# ModLCDDisplay.net
KiCad netlist of a schematic drawn in Altium Designer
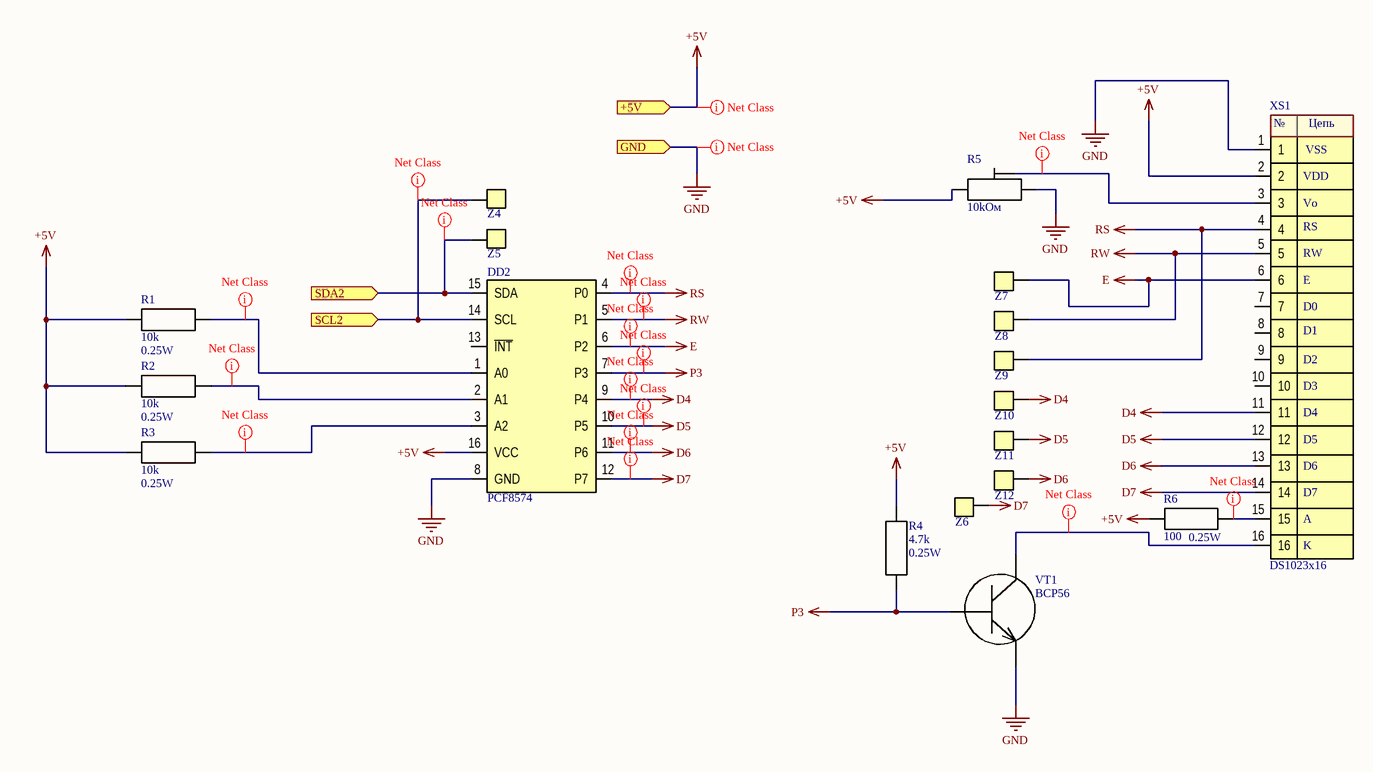
[diagram p0: ModLCDDisplay.SchDoc]

(export (version "E")
  (design (tool "Eeschema 10.0.6"))
  (components
    (comp (ref "DD2")
      (value "PCF8574")
      (footprint "SO-16")
      (fields (field (name "PART NUMBER") "PCF8574DW") (field (name "MANUFACTURER") "Texas Instruments"))
      (libsource (lib "SchlibUGO") (part "PCF8574"))
    )
    (comp (ref "R1")
      (value "10k")
      (footprint "1206")
      (fields
        (field (name "MANUFACTURER") "YAGEO")
        (field (name "PART NUMBER") "RC1206FR-0710KL")
        (field (name "POWER") "0.25W")
      )
      (libsource (lib "SchlibUGO") (part "Resistor"))
    )
    (comp (ref "R2")
      (value "10k")
      (footprint "1206")
      (fields
        (field (name "MANUFACTURER") "YAGEO")
        (field (name "PART NUMBER") "RC1206FR-0710KL")
        (field (name "POWER") "0.25W")
      )
      (libsource (lib "SchlibUGO") (part "Resistor"))
    )
    (comp (ref "R3")
      (value "10k")
      (footprint "1206")
      (fields
        (field (name "MANUFACTURER") "YAGEO")
        (field (name "PART NUMBER") "RC1206FR-0710KL")
        (field (name "POWER") "0.25W")
      )
      (libsource (lib "SchlibUGO") (part "Resistor"))
    )
    (comp (ref "R4")
      (value "4.7k")
      (footprint "1206")
      (fields
        (field (name "MANUFACTURER") "YAGEO")
        (field (name "PART NUMBER") "RC1206JR-074K7L")
        (field (name "POWER") "0.25W")
        (field (name "Comment") "4k7")
      )
      (libsource (lib "SchlibUGO") (part "Resistor"))
    )
    (comp (ref "R5")
      (value "10kОм")
      (footprint "3006P")
      (fields
        (field (name "PART NUMBER") "3006-103-Z-LF")
        (field (name "MANUFACTURER") "Bours")
        (field (name "POWER") "0,125W")
      )
      (libsource (lib "SchlibUGO") (part "POT"))
    )
    (comp (ref "R6")
      (value "100")
      (footprint "1206")
      (fields
        (field (name "MANUFACTURER") "YAGEO")
        (field (name "PART NUMBER") "RC1206FR-07100RL")
        (field (name "POWER") "0.25W")
      )
      (libsource (lib "SchlibUGO") (part "Resistor"))
    )
    (comp (ref "VT1")
      (value "BCP56")
      (footprint "SOT223")
      (fields (field (name "PART NUMBER") "BCP56-16") (field (name "MANUFACTURER") "NXP Semiconductors"))
      (libsource (lib "SchlibUGO") (part "BCP56-16"))
    )
    (comp (ref "XS1")
      (value "DS1023x16")
      (footprint "DS1023-2.54x16x1")
      (fields
        (field (name "MANUFACTURER") "Ningbo connfly electronic")
        (field (name "PART NUMBER") "DS1023-1*16S21")
      )
      (libsource (lib "SchlibUGO") (part "DS1023x2.54x16x1"))
    )
    (comp (ref "Z4") (value "test Point") (footprint "test Point") (libsource (lib "") (part "test Point_1")))
    (comp (ref "Z5") (value "test Point") (footprint "test Point") (libsource (lib "") (part "test Point_1")))
    (comp (ref "Z6")
      (value "test Point")
      (footprint "test Point")
      (libsource (lib "SchlibUGO") (part "test Point"))
    )
    (comp (ref "Z7")
      (value "test Point")
      (footprint "test Point")
      (libsource (lib "SchlibUGO") (part "test Point"))
    )
    (comp (ref "Z8")
      (value "test Point")
      (footprint "test Point")
      (libsource (lib "SchlibUGO") (part "test Point"))
    )
    (comp (ref "Z9")
      (value "test Point")
      (footprint "test Point")
      (libsource (lib "SchlibUGO") (part "test Point"))
    )
    (comp (ref "Z10")
      (value "test Point")
      (footprint "test Point")
      (libsource (lib "SchlibUGO") (part "test Point"))
    )
    (comp (ref "Z11")
      (value "test Point")
      (footprint "test Point")
      (libsource (lib "SchlibUGO") (part "test Point"))
    )
    (comp (ref "Z12")
      (value "test Point")
      (footprint "test Point")
      (libsource (lib "SchlibUGO") (part "test Point"))
    )
  )
  (nets
    (net (code "1") (name "+5V") (class "Default")
      (node (ref "DD2") (pin "16") (pinfunction "VCC_16") (pintype "passive"))
      (node (ref "R1") (pin "1") (pinfunction "1_1") (pintype "passive"))
      (node (ref "R2") (pin "1") (pinfunction "1_1") (pintype "passive"))
      (node (ref "R3") (pin "1") (pinfunction "1_1") (pintype "passive"))
      (node (ref "R4") (pin "2") (pinfunction "2_2") (pintype "passive"))
      (node (ref "R5") (pin "1") (pinfunction "1_1") (pintype "passive"))
      (node (ref "R6") (pin "1") (pinfunction "1_1") (pintype "passive"))
      (node (ref "XS1") (pin "2") (pinfunction "2_2") (pintype "passive"))
    )
    (net (code "2") (name "/SCL2") (class "Default")
      (node (ref "DD2") (pin "14") (pinfunction "SCL_14") (pintype "passive"))
      (node (ref "Z4") (pin "1") (pinfunction "1_1") (pintype "passive"))
    )
    (net (code "3") (name "/SDA2") (class "Default")
      (node (ref "DD2") (pin "15") (pinfunction "SDA_15") (pintype "passive"))
      (node (ref "Z5") (pin "1") (pinfunction "1_1") (pintype "passive"))
    )
    (net (code "4") (name "D4") (class "Default")
      (node (ref "DD2") (pin "9") (pinfunction "P4_9") (pintype "passive"))
      (node (ref "XS1") (pin "11") (pinfunction "11_11") (pintype "passive"))
      (node (ref "Z10") (pin "1") (pinfunction "1_1") (pintype "passive"))
    )
    (net (code "5") (name "D5") (class "Default")
      (node (ref "DD2") (pin "10") (pinfunction "P5_10") (pintype "passive"))
      (node (ref "XS1") (pin "12") (pinfunction "12_12") (pintype "passive"))
      (node (ref "Z11") (pin "1") (pinfunction "1_1") (pintype "passive"))
    )
    (net (code "6") (name "D6") (class "Default")
      (node (ref "DD2") (pin "11") (pinfunction "P6_11") (pintype "passive"))
      (node (ref "XS1") (pin "13") (pinfunction "13_13") (pintype "passive"))
      (node (ref "Z12") (pin "1") (pinfunction "1_1") (pintype "passive"))
    )
    (net (code "7") (name "D7") (class "Default")
      (node (ref "DD2") (pin "12") (pinfunction "P7_12") (pintype "passive"))
      (node (ref "XS1") (pin "14") (pinfunction "14_14") (pintype "passive"))
      (node (ref "Z6") (pin "1") (pinfunction "1_1") (pintype "passive"))
    )
    (net (code "8") (name "E") (class "Default")
      (node (ref "DD2") (pin "6") (pinfunction "P2_6") (pintype "passive"))
      (node (ref "XS1") (pin "6") (pinfunction "6_6") (pintype "passive"))
      (node (ref "Z7") (pin "1") (pinfunction "1_1") (pintype "passive"))
    )
    (net (code "9") (name "GND") (class "Default")
      (node (ref "DD2") (pin "8") (pinfunction "GND_8") (pintype "passive"))
      (node (ref "R5") (pin "3") (pinfunction "3_3") (pintype "passive"))
      (node (ref "VT1") (pin "3") (pinfunction "3_3") (pintype "passive"))
      (node (ref "XS1") (pin "1") (pinfunction "1_1") (pintype "passive"))
    )
    (net (code "10") (name "Net-(DD2-A0)") (class "Default")
      (node (ref "DD2") (pin "1") (pinfunction "A0_1") (pintype "passive"))
      (node (ref "R1") (pin "2") (pinfunction "2_2") (pintype "passive"))
    )
    (net (code "11") (name "Net-(DD2-A1)") (class "Default")
      (node (ref "DD2") (pin "2") (pinfunction "A1_2") (pintype "passive"))
      (node (ref "R2") (pin "2") (pinfunction "2_2") (pintype "passive"))
    )
    (net (code "12") (name "Net-(DD2-A2)") (class "Default")
      (node (ref "DD2") (pin "3") (pinfunction "A2_3") (pintype "passive"))
      (node (ref "R3") (pin "2") (pinfunction "2_2") (pintype "passive"))
    )
    (net (code "13") (name "Net-(R5-Pad2)") (class "Default")
      (node (ref "R5") (pin "2") (pinfunction "2_2") (pintype "passive"))
      (node (ref "XS1") (pin "3") (pinfunction "3_3") (pintype "passive"))
    )
    (net (code "14") (name "Net-(R6-Pad2)") (class "Default")
      (node (ref "R6") (pin "2") (pinfunction "2_2") (pintype "passive"))
      (node (ref "XS1") (pin "15") (pinfunction "15_15") (pintype "passive"))
    )
    (net (code "15") (name "Net-(VT1-Pad2)") (class "Default")
      (node (ref "VT1") (pin "2") (pinfunction "2_2") (pintype "passive"))
      (node (ref "XS1") (pin "16") (pinfunction "16_16") (pintype "passive"))
    )
    (net (code "16") (name "P3") (class "Default")
      (node (ref "DD2") (pin "7") (pinfunction "P3_7") (pintype "passive"))
      (node (ref "R4") (pin "1") (pinfunction "1_1") (pintype "passive"))
      (node (ref "VT1") (pin "1") (pinfunction "1_1") (pintype "passive"))
    )
    (net (code "17") (name "RS") (class "Default")
      (node (ref "DD2") (pin "4") (pinfunction "P0_4") (pintype "passive"))
      (node (ref "XS1") (pin "4") (pinfunction "4_4") (pintype "passive"))
      (node (ref "Z9") (pin "1") (pinfunction "1_1") (pintype "passive"))
    )
    (net (code "18") (name "RW") (class "Default")
      (node (ref "DD2") (pin "5") (pinfunction "P1_5") (pintype "passive"))
      (node (ref "XS1") (pin "5") (pinfunction "5_5") (pintype "passive"))
      (node (ref "Z8") (pin "1") (pinfunction "1_1") (pintype "passive"))
    )
    (net (code "19") (name "unconnected-(DD2-~{INT}-Pad13)") (class "Default")
      (node (ref "DD2") (pin "13") (pinfunction "~{INT}_13") (pintype "passive"))
    )
    (net (code "20") (name "unconnected-(XS1-Pad7)") (class "Default")
      (node (ref "XS1") (pin "7") (pinfunction "7_7") (pintype "passive"))
    )
    (net (code "21") (name "unconnected-(XS1-Pad8)") (class "Default")
      (node (ref "XS1") (pin "8") (pinfunction "8_8") (pintype "passive"))
    )
    (net (code "22") (name "unconnected-(XS1-Pad9)") (class "Default")
      (node (ref "XS1") (pin "9") (pinfunction "9_9") (pintype "passive"))
    )
    (net (code "23") (name "unconnected-(XS1-Pad10)") (class "Default")
      (node (ref "XS1") (pin "10") (pinfunction "10_10") (pintype "passive"))
    )
  )
)
